# rotor.net
KiCad netlist of a schematic drawn in EAGLE
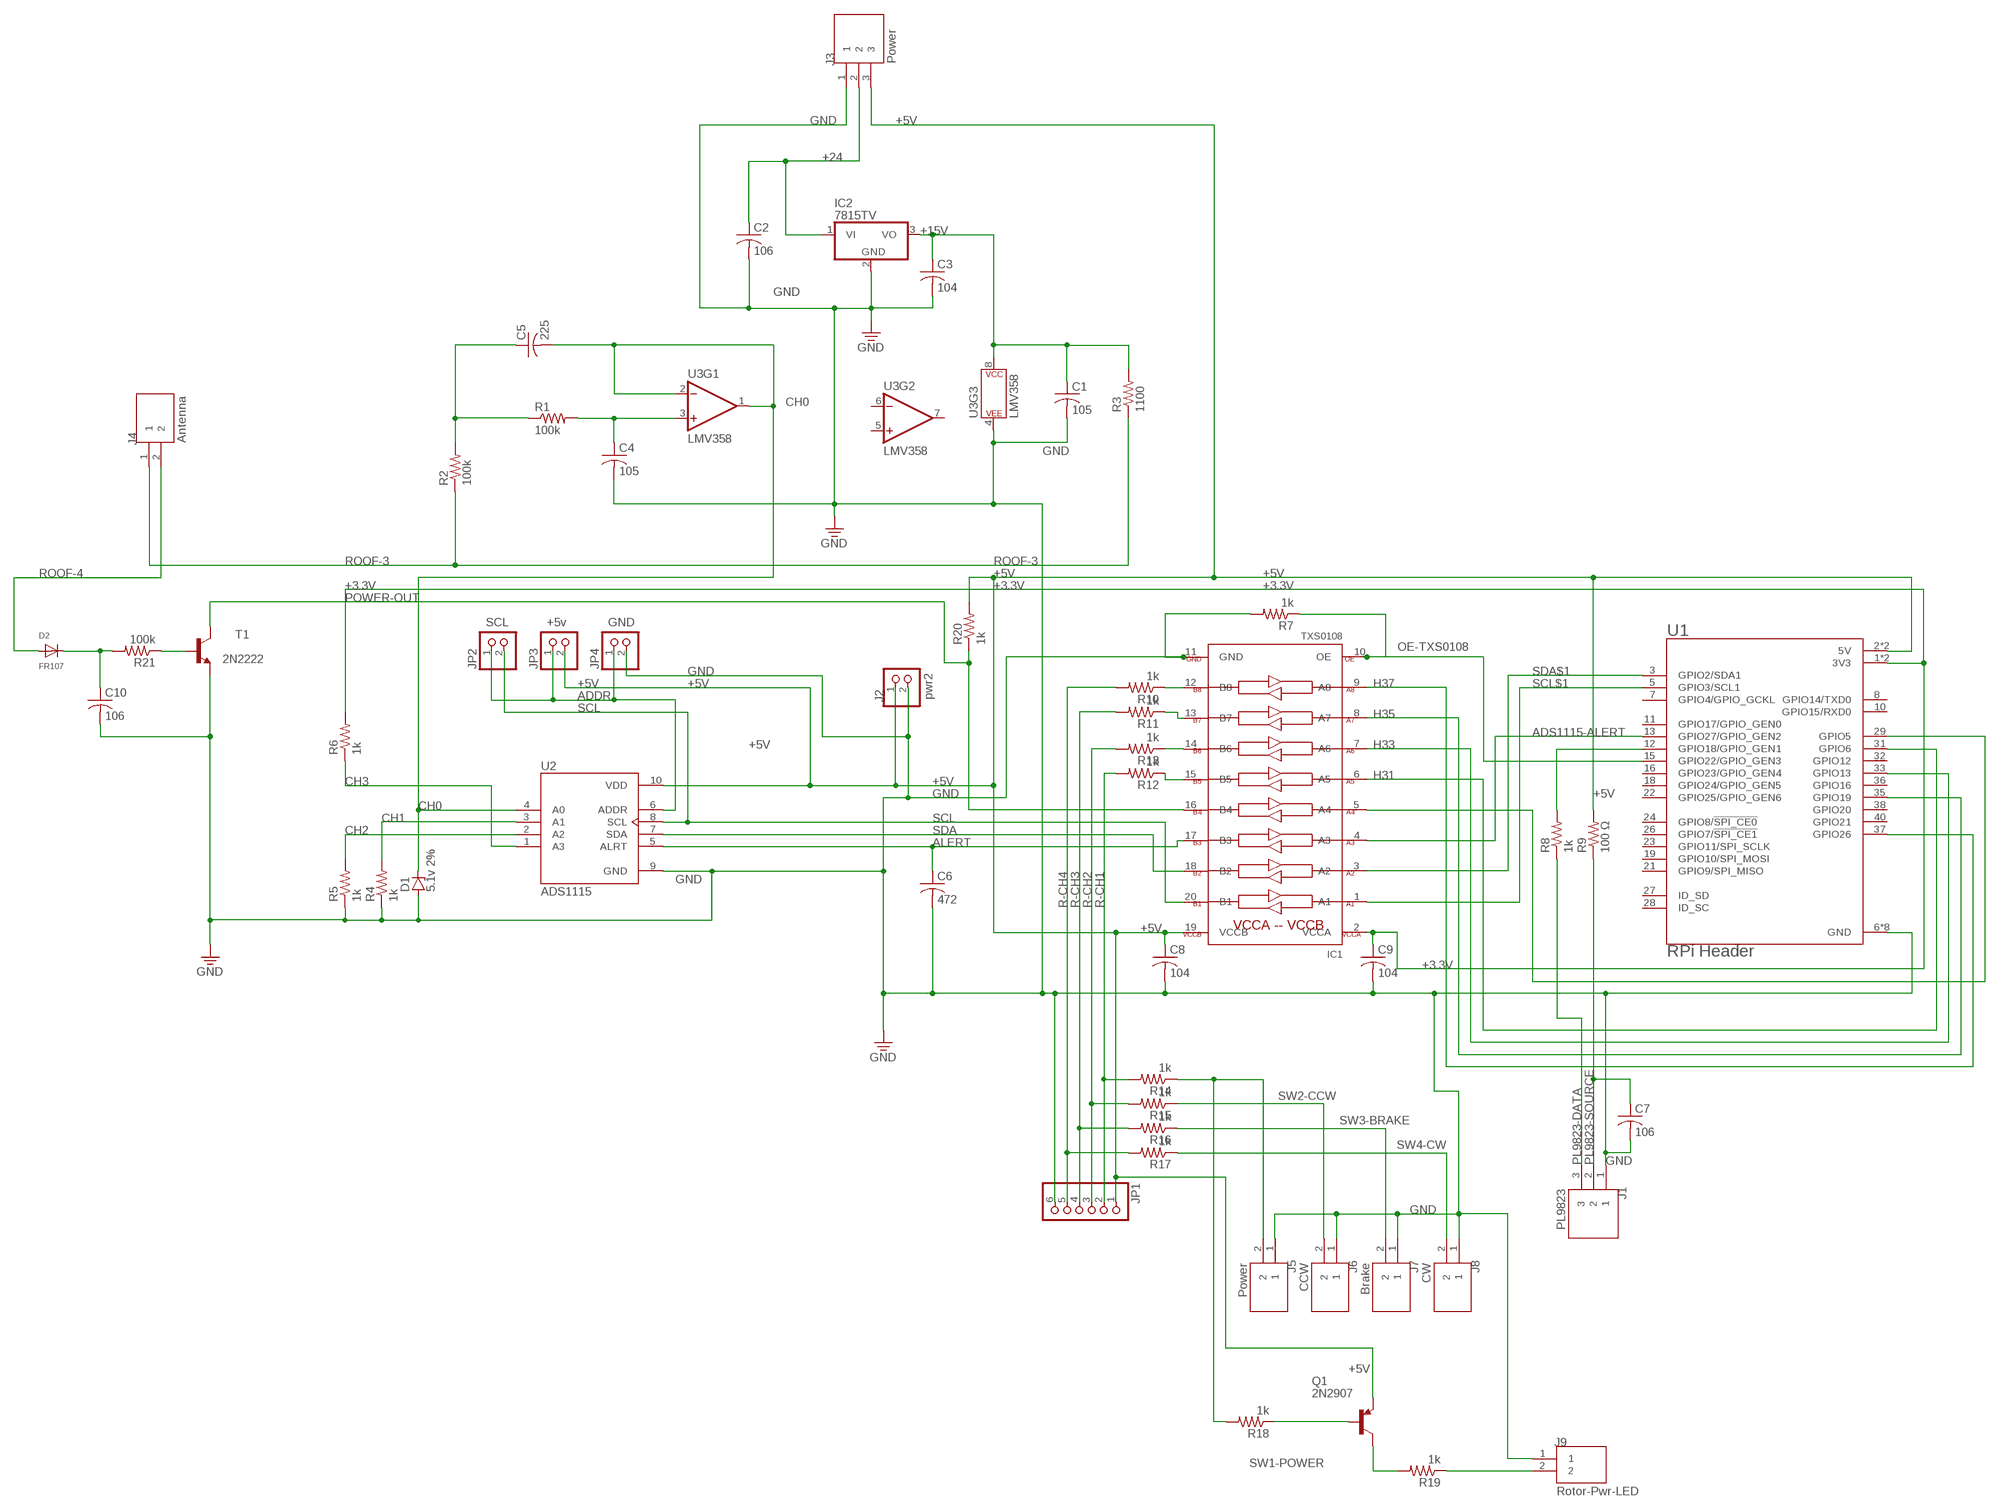
[diagram p0: schematic, sheet 1]

(export (version "E")
  (design (tool "Eeschema 10.0.6"))
  (components
    (comp (ref "C1")
      (value "105")
      (footprint "eagle-import:C0805")
      (libsource (lib "eagle-import") (part "C-USC0805"))
    )
    (comp (ref "C2")
      (value "106")
      (footprint "eagle-import:C0805")
      (libsource (lib "eagle-import") (part "C-USC0805"))
    )
    (comp (ref "C3")
      (value "104")
      (footprint "eagle-import:C0805")
      (libsource (lib "eagle-import") (part "C-USC0805"))
    )
    (comp (ref "C4")
      (value "105")
      (footprint "eagle-import:C0805")
      (libsource (lib "eagle-import") (part "C-USC0805"))
    )
    (comp (ref "C5")
      (value "225")
      (footprint "eagle-import:C0805")
      (libsource (lib "eagle-import") (part "C-USC0805"))
    )
    (comp (ref "C6")
      (value "472")
      (footprint "eagle-import:C0805")
      (libsource (lib "eagle-import") (part "C-USC0805"))
    )
    (comp (ref "C7")
      (value "106")
      (footprint "eagle-import:C0805")
      (libsource (lib "eagle-import") (part "C-USC0805"))
    )
    (comp (ref "C8")
      (value "104")
      (footprint "eagle-import:C0805")
      (libsource (lib "eagle-import") (part "C-USC0805"))
    )
    (comp (ref "C9")
      (value "104")
      (footprint "eagle-import:C0805")
      (libsource (lib "eagle-import") (part "C-USC0805"))
    )
    (comp (ref "C10")
      (value "106")
      (footprint "eagle-import:C0805")
      (libsource (lib "eagle-import") (part "C-USC0805"))
    )
    (comp (ref "D1")
      (value "5.1v 2%")
      (footprint "eagle-import:ZDIO-7.5")
      (libsource (lib "eagle-import") (part "ZENER-DIODEZD-7.5"))
    )
    (comp (ref "D2")
      (value "FR107")
      (footprint "eagle-import:SMADIODE")
      (libsource (lib "eagle-import") (part "DIODESMA"))
    )
    (comp (ref "IC1")
      (value "TXS0108")
      (footprint "eagle-import:TSSOP20")
      (fields (field (name "MF") "Texas Instruments") (field (name "MP") "TXS0108E"))
      (libsource (lib "eagle-import") (part "TXS0108EPWR"))
    )
    (comp (ref "IC2")
      (value "7815TV")
      (footprint "eagle-import:TO220V")
      (libsource (lib "eagle-import") (part "78TV15"))
    )
    (comp (ref "J1")
      (value "PL9823")
      (footprint "eagle-import:CUI_TB004-508-03BE")
      (fields (field (name "MF") "CUI Devices") (field (name "MP") "TB004 -508-03BE"))
      (libsource (lib "eagle-import") (part "TB004-508-03BE"))
    )
    (comp (ref "J2")
      (value "pwr2")
      (footprint "eagle-import:1X02")
      (libsource (lib "eagle-import") (part "pinhead_325_PINHD-1X2"))
    )
    (comp (ref "J3")
      (value "Power")
      (footprint "eagle-import:CUI_TB004-508-03BE")
      (fields (field (name "MF") "CUI Devices") (field (name "MP") "TB004 -508-03BE"))
      (libsource (lib "eagle-import") (part "TB004-508-03BE"))
    )
    (comp (ref "J4")
      (value "Antenna")
      (footprint "eagle-import:CUI_TB004-508-02BE")
      (fields (field (name "MF") "CUI Devices") (field (name "MP") "TB004-508-02BE"))
      (libsource (lib "eagle-import") (part "TB004-508-02BE"))
    )
    (comp (ref "J5")
      (value "Power")
      (footprint "eagle-import:CUI_TB004-508-02BE")
      (fields (field (name "MF") "CUI Devices") (field (name "MP") "TB004-508-02BE"))
      (libsource (lib "eagle-import") (part "TB004-508-02BE"))
    )
    (comp (ref "J6")
      (value "CCW")
      (footprint "eagle-import:CUI_TB004-508-02BE")
      (fields (field (name "MF") "CUI Devices") (field (name "MP") "TB004-508-02BE"))
      (libsource (lib "eagle-import") (part "TB004-508-02BE"))
    )
    (comp (ref "J7")
      (value "Brake")
      (footprint "eagle-import:CUI_TB004-508-02BE")
      (fields (field (name "MF") "CUI Devices") (field (name "MP") "TB004-508-02BE"))
      (libsource (lib "eagle-import") (part "TB004-508-02BE"))
    )
    (comp (ref "J8")
      (value "CW")
      (footprint "eagle-import:CUI_TB004-508-02BE")
      (fields (field (name "MF") "CUI Devices") (field (name "MP") "TB004-508-02BE"))
      (libsource (lib "eagle-import") (part "TB004-508-02BE"))
    )
    (comp (ref "J9")
      (value "Rotor-Pwr-LED")
      (footprint "eagle-import:CUI_TB004-508-02BE")
      (fields (field (name "MF") "CUI Devices") (field (name "MP") "TB004-508-02BE"))
      (libsource (lib "eagle-import") (part "TB004-508-02BE"))
    )
    (comp (ref "JP1")
      (value "PINHD-1X6")
      (footprint "eagle-import:1X06")
      (libsource (lib "eagle-import") (part "PINHD-1X6"))
    )
    (comp (ref "JP2")
      (value "SCL")
      (footprint "eagle-import:1X02-SPECIAL")
      (libsource (lib "eagle-import") (part "PINHD-1X2SPECIAL"))
    )
    (comp (ref "JP3")
      (value "+5v")
      (footprint "eagle-import:1X02-SPECIAL")
      (libsource (lib "eagle-import") (part "PINHD-1X2SPECIAL"))
    )
    (comp (ref "JP4")
      (value "GND")
      (footprint "eagle-import:1X02-SPECIAL")
      (libsource (lib "eagle-import") (part "PINHD-1X2SPECIAL"))
    )
    (comp (ref "Q1")
      (value "2N2907")
      (footprint "eagle-import:TO92-EBC-OVAL")
      (libsource (lib "eagle-import") (part "2N2907"))
    )
    (comp (ref "R1")
      (value "100k")
      (footprint "eagle-import:M0805")
      (libsource (lib "eagle-import") (part "R-US_M0805"))
    )
    (comp (ref "R2")
      (value "100k")
      (footprint "eagle-import:M0805")
      (libsource (lib "eagle-import") (part "R-US_M0805"))
    )
    (comp (ref "R3")
      (value "1100")
      (footprint "eagle-import:0204_7")
      (libsource (lib "eagle-import") (part "R-US_0204/7"))
    )
    (comp (ref "R4")
      (value "1k")
      (footprint "eagle-import:M0805")
      (libsource (lib "eagle-import") (part "R-US_M0805"))
    )
    (comp (ref "R5")
      (value "1k")
      (footprint "eagle-import:M0805")
      (libsource (lib "eagle-import") (part "R-US_M0805"))
    )
    (comp (ref "R6")
      (value "1k")
      (footprint "eagle-import:M0805")
      (libsource (lib "eagle-import") (part "R-US_M0805"))
    )
    (comp (ref "R7")
      (value "1k")
      (footprint "eagle-import:M0805")
      (libsource (lib "eagle-import") (part "R-US_M0805"))
    )
    (comp (ref "R8")
      (value "1k")
      (footprint "eagle-import:M0805")
      (libsource (lib "eagle-import") (part "R-US_M0805"))
    )
    (comp (ref "R9")
      (value "100 Ω")
      (footprint "eagle-import:M0805")
      (libsource (lib "eagle-import") (part "R-US_M0805"))
    )
    (comp (ref "R10")
      (value "1k")
      (footprint "eagle-import:M0805")
      (libsource (lib "eagle-import") (part "R-US_M0805"))
    )
    (comp (ref "R11")
      (value "1k")
      (footprint "eagle-import:M0805")
      (libsource (lib "eagle-import") (part "R-US_M0805"))
    )
    (comp (ref "R12")
      (value "1k")
      (footprint "eagle-import:M0805")
      (libsource (lib "eagle-import") (part "R-US_M0805"))
    )
    (comp (ref "R13")
      (value "1k")
      (footprint "eagle-import:M0805")
      (libsource (lib "eagle-import") (part "R-US_M0805"))
    )
    (comp (ref "R14")
      (value "1k")
      (footprint "eagle-import:M0805")
      (libsource (lib "eagle-import") (part "R-US_M0805"))
    )
    (comp (ref "R15")
      (value "1k")
      (footprint "eagle-import:M0805")
      (libsource (lib "eagle-import") (part "R-US_M0805"))
    )
    (comp (ref "R16")
      (value "1k")
      (footprint "eagle-import:M0805")
      (libsource (lib "eagle-import") (part "R-US_M0805"))
    )
    (comp (ref "R17")
      (value "1k")
      (footprint "eagle-import:M0805")
      (libsource (lib "eagle-import") (part "R-US_M0805"))
    )
    (comp (ref "R18")
      (value "1k")
      (footprint "eagle-import:M0805")
      (libsource (lib "eagle-import") (part "R-US_M0805"))
    )
    (comp (ref "R19")
      (value "1k")
      (footprint "eagle-import:M0805")
      (libsource (lib "eagle-import") (part "R-US_M0805"))
    )
    (comp (ref "R20")
      (value "1k")
      (footprint "eagle-import:M0805")
      (libsource (lib "eagle-import") (part "R-US_M0805"))
    )
    (comp (ref "R21")
      (value "100k")
      (footprint "eagle-import:M0805")
      (libsource (lib "eagle-import") (part "R-US_M0805"))
    )
    (comp (ref "T1")
      (value "2N2222")
      (footprint "eagle-import:TO92-EBC-OVAL")
      (libsource (lib "eagle-import") (part "2N2222"))
    )
    (comp (ref "U1")
      (value "RPi Header")
      (footprint "eagle-import:MODULE_RASPBERRY_PI_3B+_HDR")
      (libsource (lib "eagle-import") (part "RASPBERRY_PI_3B+_HDRMODEL_RASPBEERY_PI_3B_HDR"))
    )
    (comp (ref "U2")
      (value "ADS1115")
      (footprint "eagle-import:MODULE_1115_NARROW")
      (fields (field (name "MF") "Adafruit Industries") (field (name "MP") "1085"))
      (libsource (lib "eagle-import") (part "ADS1115-BREAKOUT-NARROW"))
    )
    (comp (ref "U3")
      (value "LMV358")
      (footprint "eagle-import:SO08")
      (libsource (lib "eagle-import") (part "LM358-SOP8SOIC"))
    )
  )
  (nets
    (net (code "1") (name "/+3.3V") (class "Default")
      (node (ref "C9") (pin "1") (pinfunction "1_1") (pintype "passive"))
      (node (ref "IC1") (pin "2") (pinfunction "VCCA_2") (pintype "power_in"))
      (node (ref "R6") (pin "2") (pinfunction "2_2") (pintype "passive"))
      (node (ref "U1") (pin "1") (pinfunction "3V3_1") (pintype "power_in"))
      (node (ref "U1") (pin "17") (pinfunction "3V3_17") (pintype "power_in"))
    )
    (net (code "2") (name "/+5V") (class "Default")
      (node (ref "C8") (pin "1") (pinfunction "1_1") (pintype "passive"))
      (node (ref "IC1") (pin "19") (pinfunction "VCCB_19") (pintype "power_in"))
      (node (ref "J2") (pin "1") (pinfunction "1_1") (pintype "passive"))
      (node (ref "J3") (pin "3") (pinfunction "3_3") (pintype "passive"))
      (node (ref "JP1") (pin "1") (pinfunction "1_1") (pintype "passive"))
      (node (ref "JP3") (pin "2") (pinfunction "2_2") (pintype "passive"))
      (node (ref "Q1") (pin "E") (pinfunction "E_E") (pintype "passive"))
      (node (ref "R20") (pin "2") (pinfunction "2_2") (pintype "passive"))
      (node (ref "R9") (pin "2") (pinfunction "2_2") (pintype "passive"))
      (node (ref "U1") (pin "2") (pinfunction "5V_2") (pintype "power_in"))
      (node (ref "U1") (pin "4") (pinfunction "5V_4") (pintype "power_in"))
      (node (ref "U2") (pin "10") (pinfunction "VDD_10") (pintype "power_in"))
    )
    (net (code "3") (name "/+15V") (class "Default")
      (node (ref "C1") (pin "1") (pinfunction "1_1") (pintype "passive"))
      (node (ref "C3") (pin "1") (pinfunction "1_1") (pintype "passive"))
      (node (ref "IC2") (pin "3") (pinfunction "VO_3") (pintype "passive"))
      (node (ref "R3") (pin "2") (pinfunction "2_2") (pintype "passive"))
      (node (ref "U3") (pin "8") (pinfunction "P$V+_8") (pintype "bidirectional"))
    )
    (net (code "4") (name "/+24") (class "Default")
      (node (ref "C2") (pin "1") (pinfunction "1_1") (pintype "passive"))
      (node (ref "IC2") (pin "1") (pinfunction "VI_1") (pintype "input"))
      (node (ref "J3") (pin "2") (pinfunction "2_2") (pintype "passive"))
    )
    (net (code "5") (name "/ADDR") (class "Default")
      (node (ref "JP2") (pin "1") (pinfunction "1_1") (pintype "passive"))
      (node (ref "JP3") (pin "1") (pinfunction "1_1") (pintype "passive"))
      (node (ref "JP4") (pin "1") (pinfunction "1_1") (pintype "passive"))
      (node (ref "U2") (pin "6") (pinfunction "ADDR_6") (pintype "input"))
    )
    (net (code "6") (name "/ADS1115-ALERT") (class "Default")
      (node (ref "IC1") (pin "4") (pinfunction "A3_4") (pintype "bidirectional"))
      (node (ref "U1") (pin "13") (pinfunction "GPIO27/GPIO_GEN2_13") (pintype "bidirectional"))
    )
    (net (code "7") (name "/ALERT") (class "Default")
      (node (ref "C6") (pin "1") (pinfunction "1_1") (pintype "passive"))
      (node (ref "IC1") (pin "17") (pinfunction "B3_17") (pintype "bidirectional"))
      (node (ref "U2") (pin "5") (pinfunction "ALRT_5") (pintype "output"))
    )
    (net (code "8") (name "/CH0") (class "Default")
      (node (ref "C5") (pin "2") (pinfunction "2_2") (pintype "passive"))
      (node (ref "D1") (pin "C") (pinfunction "C_C") (pintype "passive"))
      (node (ref "U2") (pin "4") (pinfunction "A0_4") (pintype "input"))
      (node (ref "U3") (pin "1") (pinfunction "OUT_1") (pintype "output"))
      (node (ref "U3") (pin "2") (pinfunction "-IN_2") (pintype "input"))
    )
    (net (code "9") (name "/CH1") (class "Default")
      (node (ref "R4") (pin "2") (pinfunction "2_2") (pintype "passive"))
      (node (ref "U2") (pin "3") (pinfunction "A1_3") (pintype "input"))
    )
    (net (code "10") (name "/CH2") (class "Default")
      (node (ref "R5") (pin "2") (pinfunction "2_2") (pintype "passive"))
      (node (ref "U2") (pin "2") (pinfunction "A2_2") (pintype "input"))
    )
    (net (code "11") (name "/CH3") (class "Default")
      (node (ref "R6") (pin "1") (pinfunction "1_1") (pintype "passive"))
      (node (ref "U2") (pin "1") (pinfunction "A3_1") (pintype "input"))
    )
    (net (code "12") (name "/H31") (class "Default")
      (node (ref "IC1") (pin "6") (pinfunction "A5_6") (pintype "bidirectional"))
      (node (ref "U1") (pin "31") (pinfunction "GPIO6_31") (pintype "bidirectional"))
    )
    (net (code "13") (name "/H33") (class "Default")
      (node (ref "IC1") (pin "7") (pinfunction "A6_7") (pintype "bidirectional"))
      (node (ref "U1") (pin "33") (pinfunction "GPIO13_33") (pintype "bidirectional"))
    )
    (net (code "14") (name "/H35") (class "Default")
      (node (ref "IC1") (pin "8") (pinfunction "A7_8") (pintype "bidirectional"))
      (node (ref "U1") (pin "35") (pinfunction "GPIO19_35") (pintype "bidirectional"))
    )
    (net (code "15") (name "/H37") (class "Default")
      (node (ref "IC1") (pin "9") (pinfunction "A8_9") (pintype "bidirectional"))
      (node (ref "U1") (pin "37") (pinfunction "GPIO26_37") (pintype "bidirectional"))
    )
    (net (code "16") (name "/OE-TXS0108") (class "Default")
      (node (ref "IC1") (pin "10") (pinfunction "OE_10") (pintype "input"))
      (node (ref "R7") (pin "1") (pinfunction "1_1") (pintype "passive"))
      (node (ref "U1") (pin "15") (pinfunction "GPIO22/GPIO_GEN3_15") (pintype "bidirectional"))
    )
    (net (code "17") (name "/PL9823-DATA") (class "Default")
      (node (ref "J1") (pin "3") (pinfunction "3_3") (pintype "passive"))
      (node (ref "R8") (pin "1") (pinfunction "1_1") (pintype "passive"))
    )
    (net (code "18") (name "/PL9823-SOURCE") (class "Default")
      (node (ref "C7") (pin "1") (pinfunction "1_1") (pintype "passive"))
      (node (ref "J1") (pin "2") (pinfunction "2_2") (pintype "passive"))
      (node (ref "R9") (pin "1") (pinfunction "1_1") (pintype "passive"))
    )
    (net (code "19") (name "/POWER-OUT") (class "Default")
      (node (ref "IC1") (pin "16") (pinfunction "B4_16") (pintype "bidirectional"))
      (node (ref "R20") (pin "1") (pinfunction "1_1") (pintype "passive"))
      (node (ref "T1") (pin "C") (pinfunction "C_C") (pintype "passive"))
    )
    (net (code "20") (name "/R-CH1") (class "Default")
      (node (ref "JP1") (pin "2") (pinfunction "2_2") (pintype "passive"))
      (node (ref "R12") (pin "2") (pinfunction "2_2") (pintype "passive"))
      (node (ref "R14") (pin "2") (pinfunction "2_2") (pintype "passive"))
    )
    (net (code "21") (name "/R-CH2") (class "Default")
      (node (ref "JP1") (pin "3") (pinfunction "3_3") (pintype "passive"))
      (node (ref "R13") (pin "2") (pinfunction "2_2") (pintype "passive"))
      (node (ref "R15") (pin "2") (pinfunction "2_2") (pintype "passive"))
    )
    (net (code "22") (name "/R-CH3") (class "Default")
      (node (ref "JP1") (pin "4") (pinfunction "4_4") (pintype "passive"))
      (node (ref "R11") (pin "2") (pinfunction "2_2") (pintype "passive"))
      (node (ref "R16") (pin "2") (pinfunction "2_2") (pintype "passive"))
    )
    (net (code "23") (name "/R-CH4") (class "Default")
      (node (ref "JP1") (pin "5") (pinfunction "5_5") (pintype "passive"))
      (node (ref "R10") (pin "2") (pinfunction "2_2") (pintype "passive"))
      (node (ref "R17") (pin "2") (pinfunction "2_2") (pintype "passive"))
    )
    (net (code "24") (name "/ROOF-3") (class "Default")
      (node (ref "J4") (pin "1") (pinfunction "1_1") (pintype "passive"))
      (node (ref "R2") (pin "1") (pinfunction "1_1") (pintype "passive"))
      (node (ref "R3") (pin "1") (pinfunction "1_1") (pintype "passive"))
    )
    (net (code "25") (name "/ROOF-4") (class "Default")
      (node (ref "D2") (pin "A") (pinfunction "A_A") (pintype "passive"))
      (node (ref "J4") (pin "2") (pinfunction "2_2") (pintype "passive"))
    )
    (net (code "26") (name "/SCL") (class "Default")
      (node (ref "IC1") (pin "20") (pinfunction "B1_20") (pintype "bidirectional"))
      (node (ref "JP2") (pin "2") (pinfunction "2_2") (pintype "passive"))
      (node (ref "U2") (pin "8") (pinfunction "SCL_8") (pintype "input"))
    )
    (net (code "27") (name "/SCL$1") (class "Default")
      (node (ref "IC1") (pin "1") (pinfunction "A1_1") (pintype "bidirectional"))
      (node (ref "U1") (pin "5") (pinfunction "GPIO3/SCL1_5") (pintype "bidirectional"))
    )
    (net (code "28") (name "/SDA") (class "Default")
      (node (ref "IC1") (pin "18") (pinfunction "B2_18") (pintype "bidirectional"))
      (node (ref "U2") (pin "7") (pinfunction "SDA_7") (pintype "bidirectional"))
    )
    (net (code "29") (name "/SDA$1") (class "Default")
      (node (ref "IC1") (pin "3") (pinfunction "A2_3") (pintype "bidirectional"))
      (node (ref "U1") (pin "3") (pinfunction "GPIO2/SDA1_3") (pintype "bidirectional"))
    )
    (net (code "30") (name "/SW1-POWER") (class "Default")
      (node (ref "J5") (pin "2") (pinfunction "2_2") (pintype "passive"))
      (node (ref "R14") (pin "1") (pinfunction "1_1") (pintype "passive"))
      (node (ref "R18") (pin "2") (pinfunction "2_2") (pintype "passive"))
    )
    (net (code "31") (name "/SW2-CCW") (class "Default")
      (node (ref "J6") (pin "2") (pinfunction "2_2") (pintype "passive"))
      (node (ref "R15") (pin "1") (pinfunction "1_1") (pintype "passive"))
    )
    (net (code "32") (name "/SW3-BRAKE") (class "Default")
      (node (ref "J7") (pin "2") (pinfunction "2_2") (pintype "passive"))
      (node (ref "R16") (pin "1") (pinfunction "1_1") (pintype "passive"))
    )
    (net (code "33") (name "/SW4-CW") (class "Default")
      (node (ref "J8") (pin "2") (pinfunction "2_2") (pintype "passive"))
      (node (ref "R17") (pin "1") (pinfunction "1_1") (pintype "passive"))
    )
    (net (code "34") (name "GND") (class "Default")
      (node (ref "C1") (pin "2") (pinfunction "2_2") (pintype "passive"))
      (node (ref "C10") (pin "2") (pinfunction "2_2") (pintype "passive"))
      (node (ref "C2") (pin "2") (pinfunction "2_2") (pintype "passive"))
      (node (ref "C3") (pin "2") (pinfunction "2_2") (pintype "passive"))
      (node (ref "C4") (pin "2") (pinfunction "2_2") (pintype "passive"))
      (node (ref "C6") (pin "2") (pinfunction "2_2") (pintype "passive"))
      (node (ref "C7") (pin "2") (pinfunction "2_2") (pintype "passive"))
      (node (ref "C8") (pin "2") (pinfunction "2_2") (pintype "passive"))
      (node (ref "C9") (pin "2") (pinfunction "2_2") (pintype "passive"))
      (node (ref "D1") (pin "A") (pinfunction "A_A") (pintype "passive"))
      (node (ref "IC1") (pin "11") (pinfunction "GND_11") (pintype "power_in"))
      (node (ref "IC2") (pin "2") (pinfunction "GND_2") (pintype "passive"))
      (node (ref "J1") (pin "1") (pinfunction "1_1") (pintype "passive"))
      (node (ref "J2") (pin "2") (pinfunction "2_2") (pintype "passive"))
      (node (ref "J3") (pin "1") (pinfunction "1_1") (pintype "passive"))
      (node (ref "J5") (pin "1") (pinfunction "1_1") (pintype "passive"))
      (node (ref "J6") (pin "1") (pinfunction "1_1") (pintype "passive"))
      (node (ref "J7") (pin "1") (pinfunction "1_1") (pintype "passive"))
      (node (ref "J8") (pin "1") (pinfunction "1_1") (pintype "passive"))
      (node (ref "J9") (pin "1") (pinfunction "1_1") (pintype "passive"))
      (node (ref "JP1") (pin "6") (pinfunction "6_6") (pintype "passive"))
      (node (ref "JP4") (pin "2") (pinfunction "2_2") (pintype "passive"))
      (node (ref "R4") (pin "1") (pinfunction "1_1") (pintype "passive"))
      (node (ref "R5") (pin "1") (pinfunction "1_1") (pintype "passive"))
      (node (ref "R7") (pin "2") (pinfunction "2_2") (pintype "passive"))
      (node (ref "T1") (pin "E") (pinfunction "E_E") (pintype "passive"))
      (node (ref "U1") (pin "14") (pinfunction "GND_14") (pintype "power_in"))
      (node (ref "U1") (pin "20") (pinfunction "GND_20") (pintype "power_in"))
      (node (ref "U1") (pin "25") (pinfunction "GND_25") (pintype "power_in"))
      (node (ref "U1") (pin "30") (pinfunction "GND_30") (pintype "power_in"))
      (node (ref "U1") (pin "34") (pinfunction "GND_34") (pintype "power_in"))
      (node (ref "U1") (pin "39") (pinfunction "GND_39") (pintype "power_in"))
      (node (ref "U1") (pin "6") (pinfunction "GND_6") (pintype "power_in"))
      (node (ref "U1") (pin "9") (pinfunction "GND_9") (pintype "power_in"))
      (node (ref "U2") (pin "9") (pinfunction "GND_9") (pintype "power_in"))
      (node (ref "U3") (pin "4") (pinfunction "P$V-_4") (pintype "bidirectional"))
    )
    (net (code "35") (name "Net-(C5-Pad1)") (class "Default")
      (node (ref "C5") (pin "1") (pinfunction "1_1") (pintype "passive"))
      (node (ref "R1") (pin "1") (pinfunction "1_1") (pintype "passive"))
      (node (ref "R2") (pin "2") (pinfunction "2_2") (pintype "passive"))
    )
    (net (code "36") (name "Net-(C10-Pad1)") (class "Default")
      (node (ref "C10") (pin "1") (pinfunction "1_1") (pintype "passive"))
      (node (ref "D2") (pin "C") (pinfunction "C_C") (pintype "passive"))
      (node (ref "R21") (pin "2") (pinfunction "2_2") (pintype "passive"))
    )
    (net (code "37") (name "Net-(IC1-A4)") (class "Default")
      (node (ref "IC1") (pin "5") (pinfunction "A4_5") (pintype "bidirectional"))
      (node (ref "U1") (pin "29") (pinfunction "GPIO5_29") (pintype "bidirectional"))
    )
    (net (code "38") (name "Net-(IC1-B5)") (class "Default")
      (node (ref "IC1") (pin "15") (pinfunction "B5_15") (pintype "bidirectional"))
      (node (ref "R12") (pin "1") (pinfunction "1_1") (pintype "passive"))
    )
    (net (code "39") (name "Net-(IC1-B6)") (class "Default")
      (node (ref "IC1") (pin "14") (pinfunction "B6_14") (pintype "bidirectional"))
      (node (ref "R13") (pin "1") (pinfunction "1_1") (pintype "passive"))
    )
    (net (code "40") (name "Net-(IC1-B7)") (class "Default")
      (node (ref "IC1") (pin "13") (pinfunction "B7_13") (pintype "bidirectional"))
      (node (ref "R11") (pin "1") (pinfunction "1_1") (pintype "passive"))
    )
    (net (code "41") (name "Net-(IC1-B8)") (class "Default")
      (node (ref "IC1") (pin "12") (pinfunction "B8_12") (pintype "bidirectional"))
      (node (ref "R10") (pin "1") (pinfunction "1_1") (pintype "passive"))
    )
    (net (code "42") (name "Net-(J9-Pad2)") (class "Default")
      (node (ref "J9") (pin "2") (pinfunction "2_2") (pintype "passive"))
      (node (ref "R19") (pin "1") (pinfunction "1_1") (pintype "passive"))
    )
    (net (code "43") (name "Net-(Q1-PadB)") (class "Default")
      (node (ref "Q1") (pin "B") (pinfunction "B_B") (pintype "passive"))
      (node (ref "R18") (pin "1") (pinfunction "1_1") (pintype "passive"))
    )
    (net (code "44") (name "Net-(Q1-PadC)") (class "Default")
      (node (ref "Q1") (pin "C") (pinfunction "C_C") (pintype "passive"))
      (node (ref "R19") (pin "2") (pinfunction "2_2") (pintype "passive"))
    )
    (net (code "45") (name "Net-(R21-Pad1)") (class "Default")
      (node (ref "R21") (pin "1") (pinfunction "1_1") (pintype "passive"))
      (node (ref "T1") (pin "B") (pinfunction "B_B") (pintype "passive"))
    )
    (net (code "46") (name "Net-(U1-GPIO18{slash}GPIO_GEN1)") (class "Default")
      (node (ref "R8") (pin "2") (pinfunction "2_2") (pintype "passive"))
      (node (ref "U1") (pin "12") (pinfunction "GPIO18/GPIO_GEN1_12") (pintype "bidirectional"))
    )
    (net (code "47") (name "Net-(U3A-+IN)") (class "Default")
      (node (ref "C4") (pin "1") (pinfunction "1_1") (pintype "passive"))
      (node (ref "R1") (pin "2") (pinfunction "2_2") (pintype "passive"))
      (node (ref "U3") (pin "3") (pinfunction "+IN_3") (pintype "input"))
    )
    (net (code "48") (name "unconnected-(U1-GPIO4{slash}GPIO_GCKL-Pad7)") (class "Default")
      (node (ref "U1") (pin "7") (pinfunction "GPIO4/GPIO_GCKL_7") (pintype "bidirectional"))
    )
    (net (code "49") (name "unconnected-(U1-GPIO7{slash}~{SPI_CE1}-Pad26)") (class "Default")
      (node (ref "U1") (pin "26") (pinfunction "GPIO7/~{SPI_CE1}_26") (pintype "bidirectional"))
    )
    (net (code "50") (name "unconnected-(U1-GPIO8{slash}~{SPI_CE0}-Pad24)") (class "Default")
      (node (ref "U1") (pin "24") (pinfunction "GPIO8/~{SPI_CE0}_24") (pintype "bidirectional"))
    )
    (net (code "51") (name "unconnected-(U1-GPIO9{slash}SPI_MISO-Pad21)") (class "Default")
      (node (ref "U1") (pin "21") (pinfunction "GPIO9/SPI_MISO_21") (pintype "bidirectional"))
    )
    (net (code "52") (name "unconnected-(U1-GPIO10{slash}SPI_MOSI-Pad19)") (class "Default")
      (node (ref "U1") (pin "19") (pinfunction "GPIO10/SPI_MOSI_19") (pintype "bidirectional"))
    )
    (net (code "53") (name "unconnected-(U1-GPIO11{slash}SPI_SCLK-Pad23)") (class "Default")
      (node (ref "U1") (pin "23") (pinfunction "GPIO11/SPI_SCLK_23") (pintype "bidirectional"))
    )
    (net (code "54") (name "unconnected-(U1-GPIO12-Pad32)") (class "Default")
      (node (ref "U1") (pin "32") (pinfunction "GPIO12_32") (pintype "bidirectional"))
    )
    (net (code "55") (name "unconnected-(U1-GPIO14{slash}TXD0-Pad8)") (class "Default")
      (node (ref "U1") (pin "8") (pinfunction "GPIO14/TXD0_8") (pintype "bidirectional"))
    )
    (net (code "56") (name "unconnected-(U1-GPIO15{slash}RXD0-Pad10)") (class "Default")
      (node (ref "U1") (pin "10") (pinfunction "GPIO15/RXD0_10") (pintype "bidirectional"))
    )
    (net (code "57") (name "unconnected-(U1-GPIO16-Pad36)") (class "Default")
      (node (ref "U1") (pin "36") (pinfunction "GPIO16_36") (pintype "bidirectional"))
    )
    (net (code "58") (name "unconnected-(U1-GPIO17{slash}GPIO_GEN0-Pad11)") (class "Default")
      (node (ref "U1") (pin "11") (pinfunction "GPIO17/GPIO_GEN0_11") (pintype "bidirectional"))
    )
    (net (code "59") (name "unconnected-(U1-GPIO20-Pad38)") (class "Default")
      (node (ref "U1") (pin "38") (pinfunction "GPIO20_38") (pintype "bidirectional"))
    )
    (net (code "60") (name "unconnected-(U1-GPIO21-Pad40)") (class "Default")
      (node (ref "U1") (pin "40") (pinfunction "GPIO21_40") (pintype "bidirectional"))
    )
    (net (code "61") (name "unconnected-(U1-GPIO23{slash}GPIO_GEN4-Pad16)") (class "Default")
      (node (ref "U1") (pin "16") (pinfunction "GPIO23/GPIO_GEN4_16") (pintype "bidirectional"))
    )
    (net (code "62") (name "unconnected-(U1-GPIO24{slash}GPIO_GEN5-Pad18)") (class "Default")
      (node (ref "U1") (pin "18") (pinfunction "GPIO24/GPIO_GEN5_18") (pintype "bidirectional"))
    )
    (net (code "63") (name "unconnected-(U1-GPIO25{slash}GPIO_GEN6-Pad22)") (class "Default")
      (node (ref "U1") (pin "22") (pinfunction "GPIO25/GPIO_GEN6_22") (pintype "bidirectional"))
    )
    (net (code "64") (name "unconnected-(U1-ID_SC-Pad28)") (class "Default")
      (node (ref "U1") (pin "28") (pinfunction "ID_SC_28") (pintype "bidirectional"))
    )
    (net (code "65") (name "unconnected-(U1-ID_SD-Pad27)") (class "Default")
      (node (ref "U1") (pin "27") (pinfunction "ID_SD_27") (pintype "bidirectional"))
    )
    (net (code "66") (name "unconnected-(U3B-+IN-Pad5)") (class "Default")
      (node (ref "U3") (pin "5") (pinfunction "+IN_5") (pintype "input"))
    )
    (net (code "67") (name "unconnected-(U3B--IN-Pad6)") (class "Default")
      (node (ref "U3") (pin "6") (pinfunction "-IN_6") (pintype "input"))
    )
    (net (code "68") (name "unconnected-(U3B-OUT-Pad7)") (class "Default")
      (node (ref "U3") (pin "7") (pinfunction "OUT_7") (pintype "output"))
    )
  )
)
